# Ethernet.net
KiCad netlist of a schematic drawn in Altium Designer
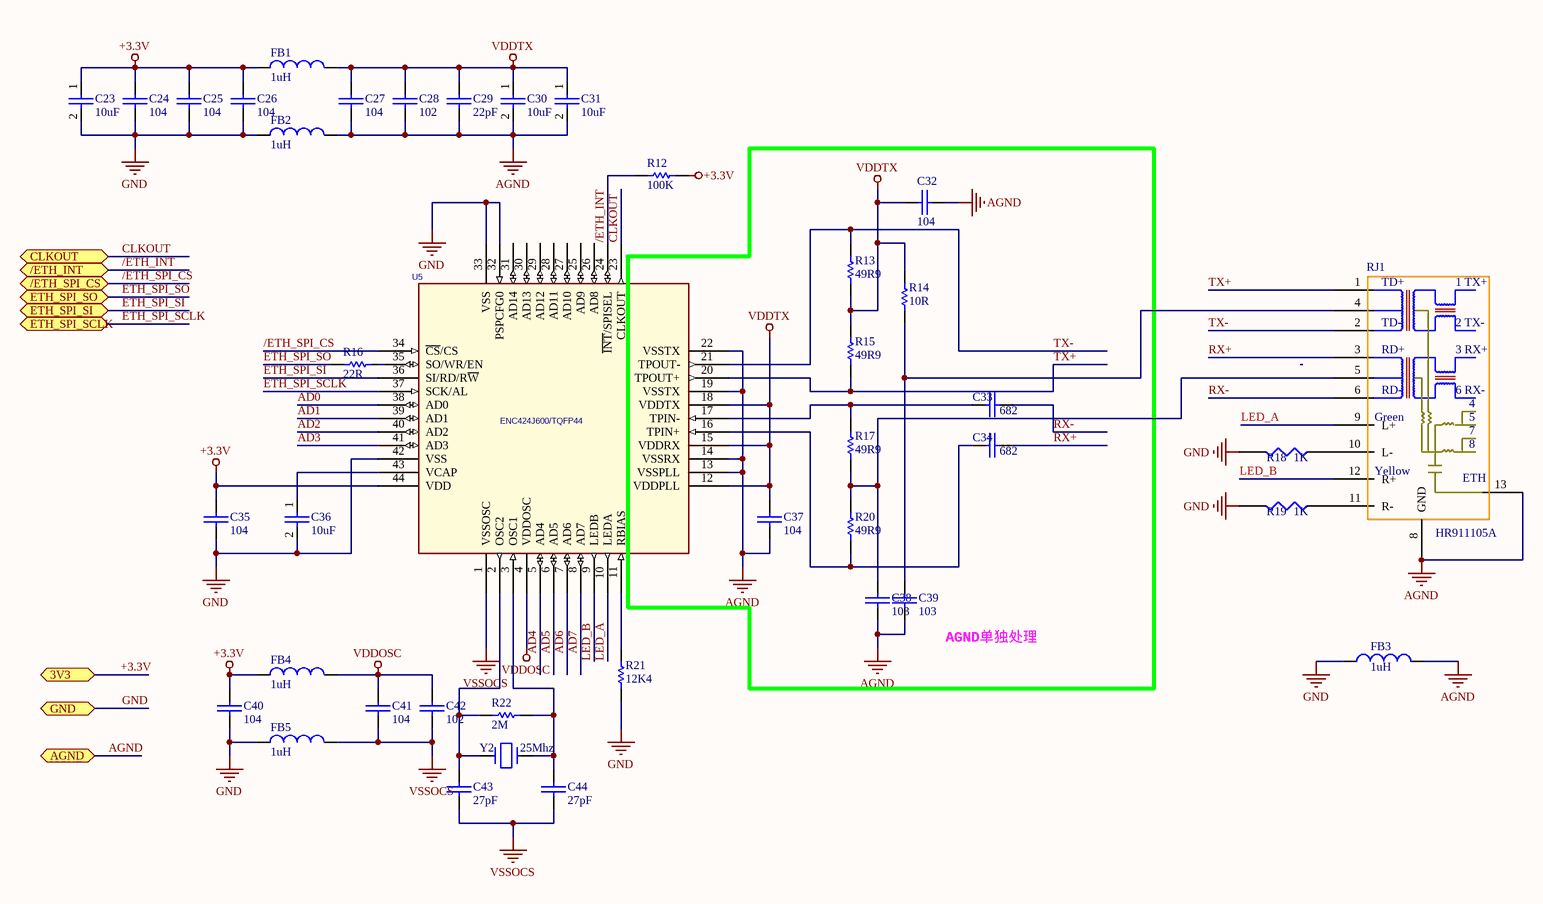
[diagram p0: Ethernet.SchDoc]

(export (version "E")
  (design (tool "Eeschema 10.0.6"))
  (components
    (comp (ref "C23")
      (value "10uF")
      (footprint "0805")
      (description "Capacitor")
      (libsource (lib "MYSTM32") (part "CAP"))
    )
    (comp (ref "C24")
      (value "104")
      (footprint "0603C")
      (description "Capacitor")
      (libsource (lib "STM32F103ZET6") (part "CAP"))
    )
    (comp (ref "C25")
      (value "104")
      (footprint "0603C")
      (description "Capacitor")
      (libsource (lib "STM32F103ZET6") (part "CAP"))
    )
    (comp (ref "C26")
      (value "104")
      (footprint "0603C")
      (description "Capacitor")
      (libsource (lib "STM32F103ZET6") (part "CAP"))
    )
    (comp (ref "C27")
      (value "104")
      (footprint "0603C")
      (description "Capacitor")
      (libsource (lib "STM32F103ZET6") (part "CAP"))
    )
    (comp (ref "C28")
      (value "102")
      (footprint "0603C")
      (description "Capacitor")
      (libsource (lib "STM32F103ZET6") (part "CAP"))
    )
    (comp (ref "C29")
      (value "22pF")
      (footprint "0603C")
      (description "Capacitor")
      (libsource (lib "STM32F103ZET6") (part "CAP"))
    )
    (comp (ref "C30")
      (value "10uF")
      (footprint "0805")
      (description "Capacitor")
      (libsource (lib "MYSTM32") (part "CAP"))
    )
    (comp (ref "C31")
      (value "10uF")
      (footprint "0805")
      (description "Capacitor")
      (libsource (lib "MYSTM32") (part "CAP"))
    )
    (comp (ref "C32")
      (value "104")
      (footprint "0603C")
      (description "Capacitor")
      (libsource (lib "STM32F103ZET6") (part "CAP"))
    )
    (comp (ref "C33")
      (value "682")
      (footprint "0603C")
      (description "Capacitor")
      (libsource (lib "STM32F103ZET6") (part "CAP"))
    )
    (comp (ref "C34")
      (value "682")
      (footprint "0603C")
      (description "Capacitor")
      (libsource (lib "STM32F103ZET6") (part "CAP"))
    )
    (comp (ref "C35")
      (value "104")
      (footprint "0603C")
      (description "Capacitor")
      (libsource (lib "STM32F103ZET6") (part "CAP"))
    )
    (comp (ref "C36")
      (value "10uF")
      (footprint "0805")
      (description "Capacitor")
      (libsource (lib "MYSTM32") (part "CAP"))
    )
    (comp (ref "C37")
      (value "104")
      (footprint "0603C")
      (description "Capacitor")
      (libsource (lib "STM32F103ZET6") (part "CAP"))
    )
    (comp (ref "C38")
      (value "103")
      (footprint "0603C")
      (description "Capacitor")
      (libsource (lib "STM32F103ZET6") (part "CAP"))
    )
    (comp (ref "C39")
      (value "103")
      (footprint "0603C")
      (description "Capacitor")
      (libsource (lib "STM32F103ZET6") (part "CAP"))
    )
    (comp (ref "C40")
      (value "104")
      (footprint "0603C")
      (description "Capacitor")
      (libsource (lib "STM32F103ZET6") (part "CAP"))
    )
    (comp (ref "C41")
      (value "104")
      (footprint "0603C")
      (description "Capacitor")
      (libsource (lib "STM32F103ZET6") (part "CAP"))
    )
    (comp (ref "C42")
      (value "102")
      (footprint "0603C")
      (description "Capacitor")
      (libsource (lib "STM32F103ZET6") (part "CAP"))
    )
    (comp (ref "C43")
      (value "27pF")
      (footprint "0603C")
      (description "Capacitor")
      (libsource (lib "STM32F103ZET6") (part "CAP"))
    )
    (comp (ref "C44")
      (value "27pF")
      (footprint "0603C")
      (description "Capacitor")
      (libsource (lib "STM32F103ZET6") (part "CAP"))
    )
    (comp (ref "FB1")
      (value "1uH")
      (footprint "0603R")
      (description "Inductor")
      (fields (field (name "PUBLISHER") "Altium Limited"))
      (libsource (lib "MYSTM32") (part "Inductor"))
    )
    (comp (ref "FB2")
      (value "1uH")
      (footprint "0603R")
      (description "Inductor")
      (fields (field (name "PUBLISHER") "Altium Limited"))
      (libsource (lib "MYSTM32") (part "Inductor"))
    )
    (comp (ref "FB3")
      (value "1uH")
      (footprint "0805")
      (description "Inductor")
      (fields (field (name "PUBLISHER") "Altium Limited"))
      (libsource (lib "MYSTM32") (part "Inductor"))
    )
    (comp (ref "FB4")
      (value "1uH")
      (footprint "0603R")
      (description "Inductor")
      (fields (field (name "PUBLISHER") "Altium Limited"))
      (libsource (lib "MYSTM32") (part "Inductor"))
    )
    (comp (ref "FB5")
      (value "1uH")
      (footprint "0603R")
      (description "Inductor")
      (fields (field (name "PUBLISHER") "Altium Limited"))
      (libsource (lib "MYSTM32") (part "Inductor"))
    )
    (comp (ref "R12")
      (value "100K")
      (footprint "0603R")
      (description "Resistor")
      (fields (field (name "PUBLISHER") "Altium Limited"))
      (libsource (lib "STM32F107VCT") (part "res1"))
    )
    (comp (ref "R13")
      (value "49R9")
      (footprint "0603R")
      (description "Resistor")
      (fields (field (name "PUBLISHER") "Altium Limited"))
      (libsource (lib "STM32F107VCT") (part "res1"))
    )
    (comp (ref "R14")
      (value "10R")
      (footprint "0603R")
      (description "Resistor")
      (fields (field (name "PUBLISHER") "Altium Limited"))
      (libsource (lib "STM32F107VCT") (part "res1"))
    )
    (comp (ref "R15")
      (value "49R9")
      (footprint "0603R")
      (description "Resistor")
      (fields (field (name "PUBLISHER") "Altium Limited"))
      (libsource (lib "STM32F107VCT") (part "res1"))
    )
    (comp (ref "R16")
      (value "22R")
      (footprint "0603R")
      (description "Resistor")
      (fields (field (name "PUBLISHER") "Altium Limited"))
      (libsource (lib "STM32F107VCT") (part "res1"))
    )
    (comp (ref "R17")
      (value "49R9")
      (footprint "0603R")
      (description "Resistor")
      (fields (field (name "PUBLISHER") "Altium Limited"))
      (libsource (lib "STM32F107VCT") (part "res1"))
    )
    (comp (ref "R18") (value "1K") (footprint "0603C") (libsource (lib "GT2440原理图库") (part "RES1")))
    (comp (ref "R19") (value "1K") (footprint "0603C") (libsource (lib "GT2440原理图库") (part "RES1")))
    (comp (ref "R20")
      (value "49R9")
      (footprint "0603R")
      (description "Resistor")
      (fields (field (name "PUBLISHER") "Altium Limited"))
      (libsource (lib "STM32F107VCT") (part "res1"))
    )
    (comp (ref "R21")
      (value "12K4")
      (footprint "0603R")
      (description "Resistor")
      (fields (field (name "PUBLISHER") "Altium Limited"))
      (libsource (lib "STM32F107VCT") (part "res1"))
    )
    (comp (ref "R22")
      (value "2M")
      (footprint "0603R")
      (description "Resistor")
      (fields (field (name "PUBLISHER") "Altium Limited"))
      (libsource (lib "STM32F107VCT") (part "res1"))
    )
    (comp (ref "RJ1")
      (value "HR911105A")
      (footprint "HR911105A")
      (libsource (lib "changyong") (part "HR911105A"))
    )
    (comp (ref "U5")
      (value "ENC424J600/TQFP44")
      (footprint "TQFP44")
      (libsource (lib "*") (part "ENC424J600/TQFP44"))
    )
    (comp (ref "Y2") (value "25Mhz") (footprint "XTAL") (libsource (lib "GT2440原理图库") (part "CRYSTAL")))
  )
  (nets
    (net (code "1") (name "+3.3V") (class "Default")
      (node (ref "C23") (pin "1") (pinfunction "1_1") (pintype "passive"))
      (node (ref "C24") (pin "2") (pinfunction "2_2") (pintype "passive"))
      (node (ref "C25") (pin "2") (pinfunction "2_2") (pintype "passive"))
      (node (ref "C26") (pin "2") (pinfunction "2_2") (pintype "passive"))
      (node (ref "C35") (pin "2") (pinfunction "2_2") (pintype "passive"))
      (node (ref "C40") (pin "2") (pinfunction "2_2") (pintype "passive"))
      (node (ref "FB1") (pin "1") (pinfunction "1_1") (pintype "passive"))
      (node (ref "FB4") (pin "1") (pinfunction "1_1") (pintype "passive"))
      (node (ref "R12") (pin "2") (pinfunction "2_2") (pintype "passive"))
      (node (ref "U5") (pin "44") (pinfunction "VDD_44") (pintype "power_in"))
    )
    (net (code "2") (name "/AD0") (class "Default")
      (node (ref "U5") (pin "38") (pinfunction "AD0_38") (pintype "bidirectional"))
    )
    (net (code "3") (name "/AD1") (class "Default")
      (node (ref "U5") (pin "39") (pinfunction "AD1_39") (pintype "bidirectional"))
    )
    (net (code "4") (name "/AD2") (class "Default")
      (node (ref "U5") (pin "40") (pinfunction "AD2_40") (pintype "bidirectional"))
    )
    (net (code "5") (name "/AD3") (class "Default")
      (node (ref "U5") (pin "41") (pinfunction "AD3_41") (pintype "bidirectional"))
    )
    (net (code "6") (name "/AD4") (class "Default")
      (node (ref "U5") (pin "5") (pinfunction "AD4_5") (pintype "bidirectional"))
    )
    (net (code "7") (name "/AD5") (class "Default")
      (node (ref "U5") (pin "6") (pinfunction "AD5_6") (pintype "bidirectional"))
    )
    (net (code "8") (name "/AD6") (class "Default")
      (node (ref "U5") (pin "7") (pinfunction "AD6_7") (pintype "bidirectional"))
    )
    (net (code "9") (name "/AD7") (class "Default")
      (node (ref "U5") (pin "8") (pinfunction "AD7_8") (pintype "bidirectional"))
    )
    (net (code "10") (name "/CLKOUT") (class "Default")
      (node (ref "U5") (pin "23") (pinfunction "CLKOUT_23") (pintype "output"))
    )
    (net (code "11") (name "/ETH_SPI_SCLK") (class "Default")
      (node (ref "U5") (pin "37") (pinfunction "SCK/AL_37") (pintype "input"))
    )
    (net (code "12") (name "/ETH_SPI_SI") (class "Default")
      (node (ref "U5") (pin "36") (pinfunction "SI/RD/R~{W}_36") (pintype "passive"))
    )
    (net (code "13") (name "/ETH_SPI_SO") (class "Default")
      (node (ref "R16") (pin "1") (pinfunction "1_1") (pintype "passive"))
    )
    (net (code "14") (name "/LED_A") (class "Default")
      (node (ref "RJ1") (pin "9") (pinfunction "L+_9") (pintype "passive"))
      (node (ref "U5") (pin "10") (pinfunction "LEDA_10") (pintype "output"))
    )
    (net (code "15") (name "/LED_B") (class "Default")
      (node (ref "RJ1") (pin "12") (pinfunction "R+_12") (pintype "passive"))
      (node (ref "U5") (pin "9") (pinfunction "LEDB_9") (pintype "output"))
    )
    (net (code "16") (name "/RX+") (class "Default")
      (node (ref "C34") (pin "1") (pinfunction "1_1") (pintype "passive"))
      (node (ref "RJ1") (pin "3") (pintype "passive"))
    )
    (net (code "17") (name "/RX-") (class "Default")
      (node (ref "C33") (pin "1") (pinfunction "1_1") (pintype "passive"))
      (node (ref "RJ1") (pin "6") (pintype "passive"))
    )
    (net (code "18") (name "/TX+") (class "Default")
      (node (ref "R15") (pin "1") (pinfunction "1_1") (pintype "passive"))
      (node (ref "RJ1") (pin "1") (pintype "passive"))
      (node (ref "U5") (pin "20") (pinfunction "TPOUT+_20") (pintype "output"))
    )
    (net (code "19") (name "/TX-") (class "Default")
      (node (ref "R13") (pin "2") (pinfunction "2_2") (pintype "passive"))
      (node (ref "RJ1") (pin "2") (pintype "passive"))
      (node (ref "U5") (pin "21") (pinfunction "TPOUT-_21") (pintype "output"))
    )
    (net (code "20") (name "/{slash}ETH_INT") (class "Default")
      (node (ref "R12") (pin "1") (pinfunction "1_1") (pintype "passive"))
      (node (ref "U5") (pin "24") (pinfunction "~{INT}/SPISEL_24") (pintype "bidirectional"))
    )
    (net (code "21") (name "/{slash}ETH_SPI_CS") (class "Default")
      (node (ref "U5") (pin "34") (pinfunction "~{CS}/CS_34") (pintype "input"))
    )
    (net (code "22") (name "AGND") (class "Default")
      (node (ref "C27") (pin "1") (pinfunction "1_1") (pintype "passive"))
      (node (ref "C28") (pin "1") (pinfunction "1_1") (pintype "passive"))
      (node (ref "C29") (pin "1") (pinfunction "1_1") (pintype "passive"))
      (node (ref "C30") (pin "2") (pinfunction "2_2") (pintype "passive"))
      (node (ref "C31") (pin "2") (pinfunction "2_2") (pintype "passive"))
      (node (ref "C32") (pin "1") (pinfunction "1_1") (pintype "passive"))
      (node (ref "C37") (pin "1") (pinfunction "1_1") (pintype "passive"))
      (node (ref "C38") (pin "1") (pinfunction "1_1") (pintype "passive"))
      (node (ref "C39") (pin "1") (pinfunction "1_1") (pintype "passive"))
      (node (ref "FB2") (pin "2") (pinfunction "2_2") (pintype "passive"))
      (node (ref "FB3") (pin "2") (pinfunction "2_2") (pintype "passive"))
      (node (ref "RJ1") (pin "13") (pintype "passive"))
      (node (ref "RJ1") (pin "8") (pinfunction "GND_8") (pintype "passive"))
      (node (ref "U5") (pin "13") (pinfunction "VSSPLL_13") (pintype "power_in"))
      (node (ref "U5") (pin "14") (pinfunction "VSSRX_14") (pintype "power_in"))
      (node (ref "U5") (pin "19") (pinfunction "VSSTX_19") (pintype "power_in"))
      (node (ref "U5") (pin "22") (pinfunction "VSSTX_22") (pintype "power_in"))
    )
    (net (code "23") (name "GND") (class "Default")
      (node (ref "C23") (pin "2") (pinfunction "2_2") (pintype "passive"))
      (node (ref "C24") (pin "1") (pinfunction "1_1") (pintype "passive"))
      (node (ref "C25") (pin "1") (pinfunction "1_1") (pintype "passive"))
      (node (ref "C26") (pin "1") (pinfunction "1_1") (pintype "passive"))
      (node (ref "C35") (pin "1") (pinfunction "1_1") (pintype "passive"))
      (node (ref "C36") (pin "2") (pinfunction "2_2") (pintype "passive"))
      (node (ref "C40") (pin "1") (pinfunction "1_1") (pintype "passive"))
      (node (ref "FB2") (pin "1") (pinfunction "1_1") (pintype "passive"))
      (node (ref "FB3") (pin "1") (pinfunction "1_1") (pintype "passive"))
      (node (ref "FB5") (pin "1") (pinfunction "1_1") (pintype "passive"))
      (node (ref "R18") (pin "2") (pinfunction "2_2") (pintype "passive"))
      (node (ref "R19") (pin "2") (pinfunction "2_2") (pintype "passive"))
      (node (ref "R21") (pin "2") (pinfunction "2_2") (pintype "passive"))
      (node (ref "U5") (pin "32") (pinfunction "PSPCFG0_32") (pintype "input"))
      (node (ref "U5") (pin "33") (pinfunction "VSS_33") (pintype "power_in"))
      (node (ref "U5") (pin "42") (pinfunction "VSS_42") (pintype "power_in"))
    )
    (net (code "24") (name "Net-(C38-Pad2)") (class "Default")
      (node (ref "C38") (pin "2") (pinfunction "2_2") (pintype "passive"))
      (node (ref "R17") (pin "1") (pinfunction "1_1") (pintype "passive"))
      (node (ref "R20") (pin "2") (pinfunction "2_2") (pintype "passive"))
      (node (ref "RJ1") (pin "5") (pintype "passive"))
    )
    (net (code "25") (name "Net-(C39-Pad2)") (class "Default")
      (node (ref "C39") (pin "2") (pinfunction "2_2") (pintype "passive"))
      (node (ref "R14") (pin "1") (pinfunction "1_1") (pintype "passive"))
      (node (ref "RJ1") (pin "4") (pintype "passive"))
    )
    (net (code "26") (name "Net-(RJ1-L-)") (class "Default")
      (node (ref "R18") (pin "1") (pinfunction "1_1") (pintype "passive"))
      (node (ref "RJ1") (pin "10") (pinfunction "L-_10") (pintype "passive"))
    )
    (net (code "27") (name "Net-(RJ1-R-)") (class "Default")
      (node (ref "R19") (pin "1") (pinfunction "1_1") (pintype "passive"))
      (node (ref "RJ1") (pin "11") (pinfunction "R-_11") (pintype "passive"))
    )
    (net (code "28") (name "Net-(U5-OSC1)") (class "Default")
      (node (ref "C44") (pin "2") (pinfunction "2_2") (pintype "passive"))
      (node (ref "R22") (pin "1") (pinfunction "1_1") (pintype "passive"))
      (node (ref "U5") (pin "3") (pinfunction "OSC1_3") (pintype "input"))
      (node (ref "Y2") (pin "1") (pintype "passive"))
    )
    (net (code "29") (name "Net-(U5-OSC2)") (class "Default")
      (node (ref "C43") (pin "2") (pinfunction "2_2") (pintype "passive"))
      (node (ref "R22") (pin "2") (pinfunction "2_2") (pintype "passive"))
      (node (ref "U5") (pin "2") (pinfunction "OSC2_2") (pintype "output"))
      (node (ref "Y2") (pin "2") (pintype "passive"))
    )
    (net (code "30") (name "Net-(U5-RBIAS)") (class "Default")
      (node (ref "R21") (pin "1") (pinfunction "1_1") (pintype "passive"))
      (node (ref "U5") (pin "11") (pinfunction "RBIAS_11") (pintype "input"))
    )
    (net (code "31") (name "Net-(U5-SO{slash}WR{slash}EN)") (class "Default")
      (node (ref "R16") (pin "2") (pinfunction "2_2") (pintype "passive"))
      (node (ref "U5") (pin "35") (pinfunction "SO/WR/EN_35") (pintype "bidirectional"))
    )
    (net (code "32") (name "Net-(U5-TPIN+)") (class "Default")
      (node (ref "C34") (pin "2") (pinfunction "2_2") (pintype "passive"))
      (node (ref "R20") (pin "1") (pinfunction "1_1") (pintype "passive"))
      (node (ref "U5") (pin "16") (pinfunction "TPIN+_16") (pintype "input"))
    )
    (net (code "33") (name "Net-(U5-TPIN-)") (class "Default")
      (node (ref "C33") (pin "2") (pinfunction "2_2") (pintype "passive"))
      (node (ref "R17") (pin "2") (pinfunction "2_2") (pintype "passive"))
      (node (ref "U5") (pin "17") (pinfunction "TPIN-_17") (pintype "input"))
    )
    (net (code "34") (name "Net-(U5-VCAP)") (class "Default")
      (node (ref "C36") (pin "1") (pinfunction "1_1") (pintype "passive"))
      (node (ref "U5") (pin "43") (pinfunction "VCAP_43") (pintype "passive"))
    )
    (net (code "35") (name "VDDOSC") (class "Default")
      (node (ref "C41") (pin "2") (pinfunction "2_2") (pintype "passive"))
      (node (ref "C42") (pin "2") (pinfunction "2_2") (pintype "passive"))
      (node (ref "FB4") (pin "2") (pinfunction "2_2") (pintype "passive"))
      (node (ref "U5") (pin "4") (pinfunction "VDDOSC_4") (pintype "power_in"))
    )
    (net (code "36") (name "VDDTX") (class "Default")
      (node (ref "C27") (pin "2") (pinfunction "2_2") (pintype "passive"))
      (node (ref "C28") (pin "2") (pinfunction "2_2") (pintype "passive"))
      (node (ref "C29") (pin "2") (pinfunction "2_2") (pintype "passive"))
      (node (ref "C30") (pin "1") (pinfunction "1_1") (pintype "passive"))
      (node (ref "C31") (pin "1") (pinfunction "1_1") (pintype "passive"))
      (node (ref "C32") (pin "2") (pinfunction "2_2") (pintype "passive"))
      (node (ref "C37") (pin "2") (pinfunction "2_2") (pintype "passive"))
      (node (ref "FB1") (pin "2") (pinfunction "2_2") (pintype "passive"))
      (node (ref "R13") (pin "1") (pinfunction "1_1") (pintype "passive"))
      (node (ref "R14") (pin "2") (pinfunction "2_2") (pintype "passive"))
      (node (ref "R15") (pin "2") (pinfunction "2_2") (pintype "passive"))
      (node (ref "U5") (pin "12") (pinfunction "VDDPLL_12") (pintype "power_in"))
      (node (ref "U5") (pin "15") (pinfunction "VDDRX_15") (pintype "power_in"))
      (node (ref "U5") (pin "18") (pinfunction "VDDTX_18") (pintype "power_in"))
    )
    (net (code "37") (name "VSSOCS") (class "Default")
      (node (ref "C41") (pin "1") (pinfunction "1_1") (pintype "passive"))
      (node (ref "C42") (pin "1") (pinfunction "1_1") (pintype "passive"))
      (node (ref "C43") (pin "1") (pinfunction "1_1") (pintype "passive"))
      (node (ref "C44") (pin "1") (pinfunction "1_1") (pintype "passive"))
      (node (ref "FB5") (pin "2") (pinfunction "2_2") (pintype "passive"))
      (node (ref "U5") (pin "1") (pinfunction "VSSOSC_1") (pintype "power_in"))
    )
    (net (code "38") (name "unconnected-(U5-AD8-Pad26)") (class "Default")
      (node (ref "U5") (pin "26") (pinfunction "AD8_26") (pintype "bidirectional"))
    )
    (net (code "39") (name "unconnected-(U5-AD9-Pad25)") (class "Default")
      (node (ref "U5") (pin "25") (pinfunction "AD9_25") (pintype "bidirectional"))
    )
    (net (code "40") (name "unconnected-(U5-AD10-Pad27)") (class "Default")
      (node (ref "U5") (pin "27") (pinfunction "AD10_27") (pintype "bidirectional"))
    )
    (net (code "41") (name "unconnected-(U5-AD11-Pad28)") (class "Default")
      (node (ref "U5") (pin "28") (pinfunction "AD11_28") (pintype "bidirectional"))
    )
    (net (code "42") (name "unconnected-(U5-AD12-Pad29)") (class "Default")
      (node (ref "U5") (pin "29") (pinfunction "AD12_29") (pintype "bidirectional"))
    )
    (net (code "43") (name "unconnected-(U5-AD13-Pad30)") (class "Default")
      (node (ref "U5") (pin "30") (pinfunction "AD13_30") (pintype "bidirectional"))
    )
    (net (code "44") (name "unconnected-(U5-AD14-Pad31)") (class "Default")
      (node (ref "U5") (pin "31") (pinfunction "AD14_31") (pintype "bidirectional"))
    )
  )
)
